# SoundChip.net
KiCad netlist of a schematic drawn in Altium Designer
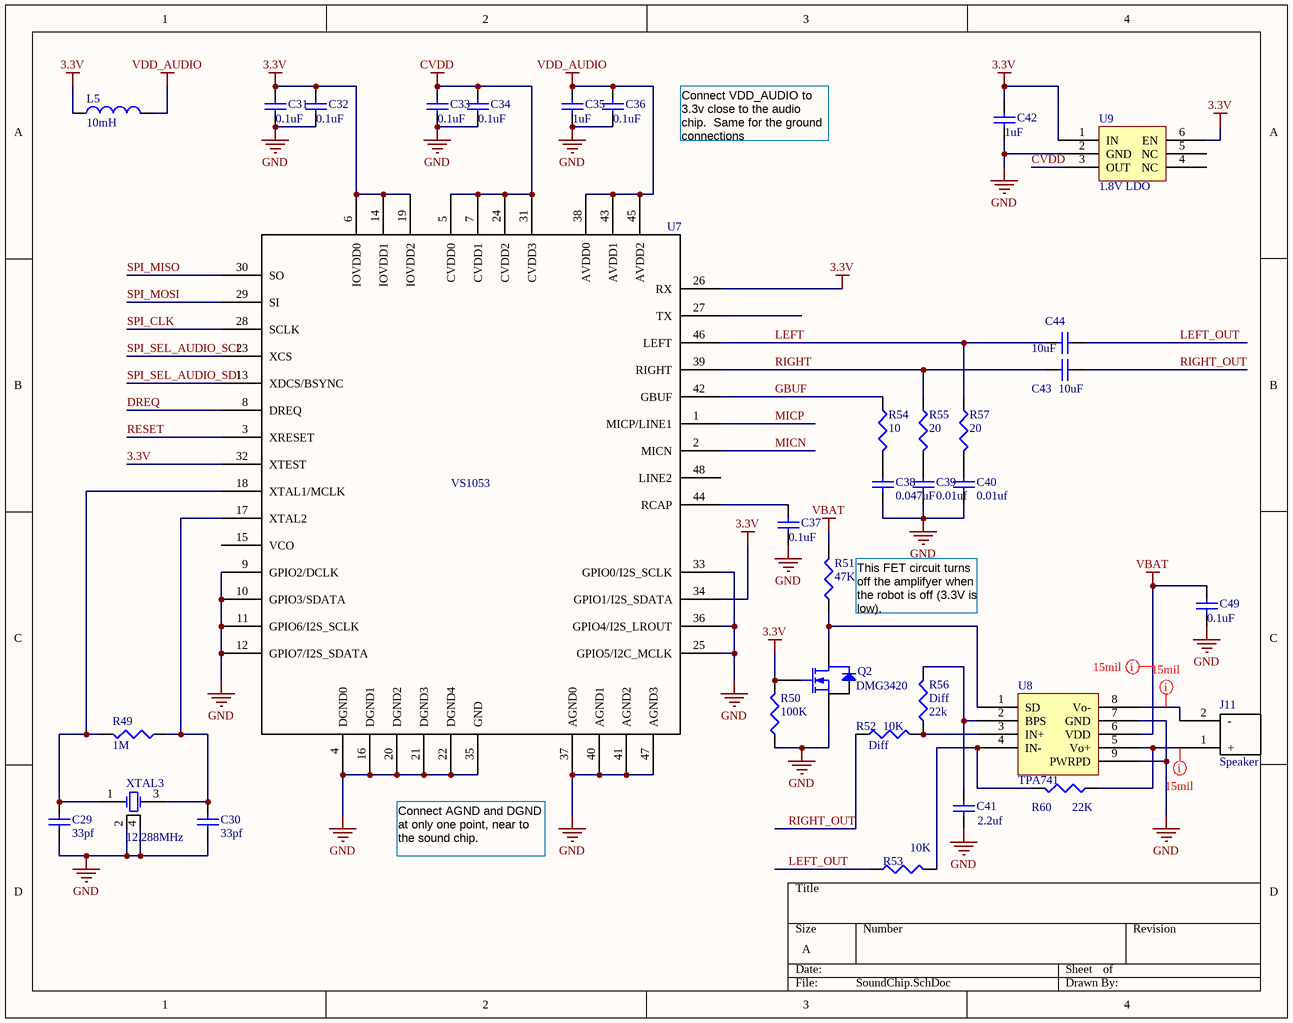
[diagram p0: SoundChip.SchDoc]

(export (version "E")
  (design (tool "Eeschema 10.0.6"))
  (components
    (comp (ref "C29")
      (value "33pf")
      (footprint "CAPC1005L")
      (description "Capacitor (Semiconductor SIM Model)")
      (fields
        (field (name "PART NUMBER") "GRM1555C1H330JA01D")
        (field (name "MANUFACTURER") "Murata")
        (field (name "PUBLISHER") "Altium Limited")
      )
      (libsource (lib "Miscellaneous Devices") (part "Cap Semi"))
    )
    (comp (ref "C30")
      (value "33pf")
      (footprint "CAPC1005L")
      (description "Capacitor (Semiconductor SIM Model)")
      (fields
        (field (name "PART NUMBER") "GRM1555C1H330JA01D")
        (field (name "MANUFACTURER") "Murata")
        (field (name "PUBLISHER") "Altium Limited")
      )
      (libsource (lib "Miscellaneous Devices") (part "Cap Semi"))
    )
    (comp (ref "C31")
      (value "0.1uF")
      (footprint "CAPC1005L")
      (description "Capacitor (Semiconductor SIM Model)")
      (fields
        (field (name "PART NUMBER") "C1005X5R1A104M050BA")
        (field (name "MANUFACTURER") "TDK")
        (field (name "PUBLISHER") "Altium Limited")
      )
      (libsource (lib "Miscellaneous Devices") (part "Cap Semi"))
    )
    (comp (ref "C32")
      (value "0.1uF")
      (footprint "CAPC1005L")
      (description "Capacitor (Semiconductor SIM Model)")
      (fields
        (field (name "PART NUMBER") "C1005X5R1A104M050BA")
        (field (name "MANUFACTURER") "TDK")
        (field (name "PUBLISHER") "Altium Limited")
      )
      (libsource (lib "Miscellaneous Devices") (part "Cap Semi"))
    )
    (comp (ref "C33")
      (value "0.1uF")
      (footprint "CAPC1005L")
      (description "Capacitor (Semiconductor SIM Model)")
      (fields
        (field (name "PART NUMBER") "C1005X5R1A104M050BA")
        (field (name "MANUFACTURER") "TDK")
        (field (name "PUBLISHER") "Altium Limited")
      )
      (libsource (lib "Miscellaneous Devices") (part "Cap Semi"))
    )
    (comp (ref "C34")
      (value "0.1uF")
      (footprint "CAPC1005L")
      (description "Capacitor (Semiconductor SIM Model)")
      (fields
        (field (name "PART NUMBER") "C1005X5R1A104M050BA")
        (field (name "MANUFACTURER") "TDK")
        (field (name "PUBLISHER") "Altium Limited")
      )
      (libsource (lib "Miscellaneous Devices") (part "Cap Semi"))
    )
    (comp (ref "C35")
      (value "1uF")
      (footprint "CAPC1608L")
      (description "Capacitor (Semiconductor SIM Model)")
      (fields
        (field (name "PART NUMBER") "C1608Y5V1C105Z")
        (field (name "MANUFACTURER") "TDK")
        (field (name "PUBLISHER") "Altium Limited")
      )
      (libsource (lib "Miscellaneous Devices") (part "Cap Semi"))
    )
    (comp (ref "C36")
      (value "0.1uF")
      (footprint "CAPC1005L")
      (description "Capacitor (Semiconductor SIM Model)")
      (fields
        (field (name "PART NUMBER") "C1005X5R1A104M050BA")
        (field (name "MANUFACTURER") "TDK")
        (field (name "PUBLISHER") "Altium Limited")
      )
      (libsource (lib "Miscellaneous Devices") (part "Cap Semi"))
    )
    (comp (ref "C37")
      (value "0.1uF")
      (footprint "CAPC1005L")
      (description "Capacitor (Semiconductor SIM Model)")
      (fields
        (field (name "PART NUMBER") "C1005X5R1A104M050BA")
        (field (name "MANUFACTURER") "TDK")
        (field (name "PUBLISHER") "Altium Limited")
      )
      (libsource (lib "Miscellaneous Devices") (part "Cap Semi"))
    )
    (comp (ref "C38")
      (value "0.047uF")
      (footprint "CAPC1005L")
      (description "Capacitor (Semiconductor SIM Model)")
      (fields
        (field (name "PART NUMBER") "CGA2BZX7R1C473K")
        (field (name "PART NUMBER_1") "CGA2B2X7R1C473K050BA")
        (field (name "PUBLISHER") "Altium Limited")
      )
      (libsource (lib "Miscellaneous Devices") (part "Cap Semi"))
    )
    (comp (ref "C39")
      (value "0.01uf")
      (footprint "CAPC1005L")
      (description "Capacitor (Semiconductor SIM Model)")
      (fields
        (field (name "PART NUMBER") "C1005X7R1C103K050BA")
        (field (name "MANUFACTURER") "TDK")
        (field (name "PUBLISHER") "Altium Limited")
      )
      (libsource (lib "Miscellaneous Devices") (part "Cap Semi"))
    )
    (comp (ref "C40")
      (value "0.01uf")
      (footprint "CAPC1005L")
      (description "Capacitor (Semiconductor SIM Model)")
      (fields
        (field (name "PART NUMBER") "C1005X7R1C103K050BA")
        (field (name "MANUFACTURER") "TDK")
        (field (name "PUBLISHER") "Altium Limited")
      )
      (libsource (lib "Miscellaneous Devices") (part "Cap Semi"))
    )
    (comp (ref "C41")
      (value "2.2uf")
      (footprint "J1-0603")
      (description "Capacitor (Semiconductor SIM Model)")
      (fields
        (field (name "PART NUMBER") "JMK107F225ZA-T")
        (field (name "MANUFACTURER") "Taiyo Yuden")
        (field (name "PUBLISHER") "Altium Limited")
      )
      (libsource (lib "Miscellaneous Devices") (part "Cap Semi"))
    )
    (comp (ref "C42")
      (value "1uF")
      (footprint "CAPC1608L")
      (description "Capacitor (Semiconductor SIM Model)")
      (fields
        (field (name "PART NUMBER") "C1608Y5V1C105Z")
        (field (name "MANUFACTURER") "TDK")
        (field (name "PUBLISHER") "Altium Limited")
      )
      (libsource (lib "Miscellaneous Devices") (part "Cap Semi"))
    )
    (comp (ref "C43")
      (value "10uF")
      (footprint "CAPC1608L")
      (description "Capacitor (Semiconductor SIM Model)")
      (fields
        (field (name "PART NUMBER") "GRM188R60J106ME47J")
        (field (name "MANUFACTURER") "Murata")
        (field (name "PUBLISHER") "Altium Limited")
      )
      (libsource (lib "Miscellaneous Devices") (part "Cap Semi"))
    )
    (comp (ref "C44")
      (value "10uF")
      (footprint "CAPC1608L")
      (description "Capacitor (Semiconductor SIM Model)")
      (fields
        (field (name "PART NUMBER") "GRM188R60J106ME47J")
        (field (name "MANUFACTURER") "Murata")
        (field (name "PUBLISHER") "Altium Limited")
      )
      (libsource (lib "Miscellaneous Devices") (part "Cap Semi"))
    )
    (comp (ref "C49")
      (value "0.1uF")
      (footprint "CAPC1005L")
      (description "Capacitor (Semiconductor SIM Model)")
      (fields
        (field (name "PART NUMBER") "C1005X5R1A104M050BA")
        (field (name "MANUFACTURER") "TDK")
        (field (name "PUBLISHER") "Altium Limited")
      )
      (libsource (lib "Miscellaneous Devices") (part "Cap Semi"))
    )
    (comp (ref "J11")
      (value "Speaker")
      (footprint "BatteryConnJST")
      (fields (field (name "PART NUMBER") "530140210") (field (name "MANUFACTURER") "Molex"))
      (libsource (lib "mrone") (part "BatteryConnJST"))
    )
    (comp (ref "L5")
      (value "10mH")
      (footprint "INDC2012L")
      (description "Inductor")
      (fields
        (field (name "PART NUMBER") "MMZ2012R102A")
        (field (name "MANUFACTURER") "TDK")
        (field (name "PUBLISHER") "Altium Limited")
      )
      (libsource (lib "Miscellaneous Devices") (part "Inductor"))
    )
    (comp (ref "Q2")
      (value "N-Mosfet")
      (footprint "SOT-23")
      (fields
        (field (name "MPN") "DMG3420")
        (field (name "PART NUMBER") "DMG3420U-7")
        (field (name "MANUFACTURER") "Diodes")
      )
      (libsource (lib "mrone") (part "N-Mosfet"))
    )
    (comp (ref "R49")
      (value "1M")
      (footprint "RESC1608L")
      (description "Resistor")
      (fields
        (field (name "PART NUMBER") "CR0603-JW-105GLF")
        (field (name "MANUFACTURER") "Bourns")
        (field (name "PUBLISHER") "Altium Limited")
      )
      (libsource (lib "Miscellaneous Devices") (part "Res3"))
    )
    (comp (ref "R50")
      (value "100K")
      (footprint "RESC1608L")
      (description "Resistor")
      (fields
        (field (name "PART NUMBER") "ERJ-3GEYJ104V")
        (field (name "MANUFACTURER") "Panasonic")
        (field (name "PUBLISHER") "Altium Limited")
      )
      (libsource (lib "Miscellaneous Devices") (part "Res3"))
    )
    (comp (ref "R51")
      (value "47K")
      (footprint "J1-0603")
      (description "Resistor")
      (fields
        (field (name "PART NUMBER") "ERJ-3GEYJ473V")
        (field (name "MANUFACTURER") "Panasonic")
        (field (name "PUBLISHER") "Altium Limited")
      )
      (libsource (lib "Miscellaneous Devices") (part "Res3"))
    )
    (comp (ref "R52")
      (value "Diff")
      (footprint "RESC1608L")
      (description "Resistor")
      (fields
        (field (name "ALTIUM_VALUE") "10K")
        (field (name "PART NUMBER") "SR03-1002")
        (field (name "MANUFACTURER") "Vishay")
        (field (name "PUBLISHER") "Altium Limited")
      )
      (libsource (lib "Miscellaneous Devices") (part "Res3"))
    )
    (comp (ref "R53")
      (value "10K")
      (footprint "RESC1608L")
      (description "Resistor")
      (fields
        (field (name "PART NUMBER") "SR03-1002")
        (field (name "MANUFACTURER") "Vishay")
        (field (name "PUBLISHER") "Altium Limited")
      )
      (libsource (lib "Miscellaneous Devices") (part "Res3"))
    )
    (comp (ref "R54")
      (value "10")
      (footprint "RESC1608L")
      (description "Resistor")
      (fields
        (field (name "PART NUMBER") "RMCF0603JT10R0")
        (field (name "MANUFACTURER") "Stackpole")
        (field (name "PUBLISHER") "Altium Limited")
      )
      (libsource (lib "Miscellaneous Devices") (part "Res3"))
    )
    (comp (ref "R55")
      (value "20")
      (footprint "RESC1608L")
      (description "Resistor")
      (fields
        (field (name "PART NUMBER") "RMCF0603FT20R0")
        (field (name "MANUFACTURER") "Stack Pole")
        (field (name "PUBLISHER") "Altium Limited")
      )
      (libsource (lib "Miscellaneous Devices") (part "Res3"))
    )
    (comp (ref "R56")
      (value "Diff")
      (footprint "RESC1608L")
      (description "Resistor")
      (fields
        (field (name "ALTIUM_VALUE") "22k")
        (field (name "MANUFACTURER") "Panasonic")
        (field (name "PUBLISHER") "Altium Limited")
      )
      (libsource (lib "Miscellaneous Devices") (part "Res3"))
    )
    (comp (ref "R57")
      (value "20")
      (footprint "RESC1608L")
      (description "Resistor")
      (fields
        (field (name "PART NUMBER") "RMCF0603FT20R0")
        (field (name "MANUFACTURER") "Stack Pole")
        (field (name "PUBLISHER") "Altium Limited")
      )
      (libsource (lib "Miscellaneous Devices") (part "Res3"))
    )
    (comp (ref "R60")
      (value "22K")
      (footprint "RESC1608L")
      (description "Resistor")
      (fields
        (field (name "PART NUMBER") "ERJ-3GEYJ223V")
        (field (name "MANUFACTURER") "Panasonic")
        (field (name "PUBLISHER") "Altium Limited")
      )
      (libsource (lib "Miscellaneous Devices") (part "Res3"))
    )
    (comp (ref "U7")
      (value "VS1053")
      (footprint "LQFP-48")
      (fields (field (name "MANUFACTURER") "VLSI Solution"))
      (libsource (lib "mrone") (part "VS1053"))
    )
    (comp (ref "U8")
      (value "TPA741")
      (footprint "audio amp")
      (fields (field (name "PART NUMBER") "TPA741DGNR") (field (name "MANUFACTURER") "TI"))
      (libsource (lib "mrone") (part "Audio Amp TPA741"))
    )
    (comp (ref "U9")
      (value "1.8V LDO")
      (footprint "WFDFN-6")
      (fields (field (name "PART NUMBER") "TLV70018DSET") (field (name "MANUFACTURER") "TI"))
      (libsource (lib "mrone") (part "1.8V_LDO"))
    )
    (comp (ref "XTAL3")
      (value "12.288MHz")
      (footprint "CRYSTAL")
      (fields (field (name "PART NUMBER") "ABM3B-12.288MHZ-10-1-U-T") (field (name "MANUFACTURER") "Abracon"))
      (libsource (lib "mrone") (part "Crystal"))
    )
  )
  (nets
    (net (code "1") (name "/DREQ") (class "Default")
      (node (ref "U7") (pin "8") (pinfunction "DREQ_8") (pintype "passive"))
    )
    (net (code "2") (name "/GBUF") (class "Default")
      (node (ref "R54") (pin "1") (pinfunction "1_1") (pintype "passive"))
      (node (ref "U7") (pin "42") (pinfunction "GBUF_42") (pintype "passive"))
    )
    (net (code "3") (name "/LEFT") (class "Default")
      (node (ref "C44") (pin "2") (pinfunction "2_2") (pintype "passive"))
      (node (ref "R57") (pin "1") (pinfunction "1_1") (pintype "passive"))
      (node (ref "U7") (pin "46") (pinfunction "LEFT_46") (pintype "passive"))
    )
    (net (code "4") (name "/LEFT_OUT") (class "Default")
      (node (ref "C44") (pin "1") (pinfunction "1_1") (pintype "passive"))
      (node (ref "R53") (pin "1") (pinfunction "1_1") (pintype "passive"))
    )
    (net (code "5") (name "/MICN") (class "Default")
      (node (ref "U7") (pin "2") (pinfunction "MICN_2") (pintype "passive"))
    )
    (net (code "6") (name "/MICP") (class "Default")
      (node (ref "U7") (pin "1") (pinfunction "MICP/LINE1_1") (pintype "passive"))
    )
    (net (code "7") (name "/RESET") (class "Default")
      (node (ref "U7") (pin "3") (pinfunction "XRESET_3") (pintype "passive"))
    )
    (net (code "8") (name "/RIGHT") (class "Default")
      (node (ref "C43") (pin "2") (pinfunction "2_2") (pintype "passive"))
      (node (ref "R55") (pin "1") (pinfunction "1_1") (pintype "passive"))
      (node (ref "U7") (pin "39") (pinfunction "RIGHT_39") (pintype "passive"))
    )
    (net (code "9") (name "/RIGHT_OUT") (class "Default")
      (node (ref "C43") (pin "1") (pinfunction "1_1") (pintype "passive"))
      (node (ref "R52") (pin "1") (pinfunction "1_1") (pintype "passive"))
    )
    (net (code "10") (name "/SPI_CLK") (class "Default")
      (node (ref "U7") (pin "28") (pinfunction "SCLK_28") (pintype "passive"))
    )
    (net (code "11") (name "/SPI_MISO") (class "Default")
      (node (ref "U7") (pin "30") (pinfunction "SO_30") (pintype "passive"))
    )
    (net (code "12") (name "/SPI_MOSI") (class "Default")
      (node (ref "U7") (pin "29") (pinfunction "SI_29") (pintype "passive"))
    )
    (net (code "13") (name "/SPI_SEL_AUDIO_SCI") (class "Default")
      (node (ref "U7") (pin "23") (pinfunction "XCS_23") (pintype "passive"))
    )
    (net (code "14") (name "/SPI_SEL_AUDIO_SDI") (class "Default")
      (node (ref "U7") (pin "13") (pinfunction "XDCS/BSYNC_13") (pintype "passive"))
    )
    (net (code "15") (name "3.3V") (class "Default")
      (node (ref "C31") (pin "2") (pinfunction "2_2") (pintype "passive"))
      (node (ref "C32") (pin "2") (pinfunction "2_2") (pintype "passive"))
      (node (ref "C42") (pin "1") (pinfunction "1_1") (pintype "passive"))
      (node (ref "L5") (pin "2") (pinfunction "2_2") (pintype "passive"))
      (node (ref "Q2") (pin "1") (pinfunction "G_1") (pintype "passive"))
      (node (ref "R50") (pin "2") (pinfunction "2_2") (pintype "passive"))
      (node (ref "U7") (pin "14") (pinfunction "IOVDD1_14") (pintype "passive"))
      (node (ref "U7") (pin "19") (pinfunction "IOVDD2_19") (pintype "passive"))
      (node (ref "U7") (pin "26") (pinfunction "RX_26") (pintype "passive"))
      (node (ref "U7") (pin "32") (pinfunction "XTEST_32") (pintype "passive"))
      (node (ref "U7") (pin "34") (pinfunction "GPIO1/I2S_SDATA_34") (pintype "passive"))
      (node (ref "U7") (pin "6") (pinfunction "IOVDD0_6") (pintype "passive"))
      (node (ref "U9") (pin "1") (pinfunction "IN_1") (pintype "passive"))
      (node (ref "U9") (pin "6") (pinfunction "EN_6") (pintype "passive"))
    )
    (net (code "16") (name "CVDD") (class "Default")
      (node (ref "C33") (pin "2") (pinfunction "2_2") (pintype "passive"))
      (node (ref "C34") (pin "2") (pinfunction "2_2") (pintype "passive"))
      (node (ref "U7") (pin "24") (pinfunction "CVDD2_24") (pintype "passive"))
      (node (ref "U7") (pin "31") (pinfunction "CVDD3_31") (pintype "passive"))
      (node (ref "U7") (pin "5") (pinfunction "CVDD0_5") (pintype "passive"))
      (node (ref "U7") (pin "7") (pinfunction "CVDD1_7") (pintype "passive"))
      (node (ref "U9") (pin "3") (pinfunction "OUT_3") (pintype "passive"))
    )
    (net (code "17") (name "GND") (class "Default")
      (node (ref "C29") (pin "2") (pinfunction "2_2") (pintype "passive"))
      (node (ref "C30") (pin "2") (pinfunction "2_2") (pintype "passive"))
      (node (ref "C31") (pin "1") (pinfunction "1_1") (pintype "passive"))
      (node (ref "C32") (pin "1") (pinfunction "1_1") (pintype "passive"))
      (node (ref "C33") (pin "1") (pinfunction "1_1") (pintype "passive"))
      (node (ref "C34") (pin "1") (pinfunction "1_1") (pintype "passive"))
      (node (ref "C35") (pin "2") (pinfunction "2_2") (pintype "passive"))
      (node (ref "C36") (pin "1") (pinfunction "1_1") (pintype "passive"))
      (node (ref "C37") (pin "1") (pinfunction "1_1") (pintype "passive"))
      (node (ref "C38") (pin "2") (pinfunction "2_2") (pintype "passive"))
      (node (ref "C39") (pin "2") (pinfunction "2_2") (pintype "passive"))
      (node (ref "C40") (pin "2") (pinfunction "2_2") (pintype "passive"))
      (node (ref "C41") (pin "1") (pinfunction "1_1") (pintype "passive"))
      (node (ref "C42") (pin "2") (pinfunction "2_2") (pintype "passive"))
      (node (ref "C49") (pin "1") (pinfunction "1_1") (pintype "passive"))
      (node (ref "Q2") (pin "2") (pinfunction "S_2") (pintype "passive"))
      (node (ref "R50") (pin "1") (pinfunction "1_1") (pintype "passive"))
      (node (ref "U7") (pin "10") (pinfunction "GPIO3/SDATA_10") (pintype "passive"))
      (node (ref "U7") (pin "11") (pinfunction "GPIO6/I2S_SCLK_11") (pintype "passive"))
      (node (ref "U7") (pin "12") (pinfunction "GPIO7/I2S_SDATA_12") (pintype "passive"))
      (node (ref "U7") (pin "16") (pinfunction "DGND1_16") (pintype "passive"))
      (node (ref "U7") (pin "20") (pinfunction "DGND2_20") (pintype "passive"))
      (node (ref "U7") (pin "21") (pinfunction "DGND3_21") (pintype "passive"))
      (node (ref "U7") (pin "22") (pinfunction "DGND4_22") (pintype "passive"))
      (node (ref "U7") (pin "25") (pinfunction "GPIO5/I2C_MCLK_25") (pintype "passive"))
      (node (ref "U7") (pin "33") (pinfunction "GPIO0/I2S_SCLK_33") (pintype "passive"))
      (node (ref "U7") (pin "35") (pinfunction "GND_35") (pintype "passive"))
      (node (ref "U7") (pin "36") (pinfunction "GPIO4/I2S_LROUT_36") (pintype "passive"))
      (node (ref "U7") (pin "37") (pinfunction "AGND0_37") (pintype "passive"))
      (node (ref "U7") (pin "4") (pinfunction "DGND0_4") (pintype "passive"))
      (node (ref "U7") (pin "40") (pinfunction "AGND1_40") (pintype "passive"))
      (node (ref "U7") (pin "41") (pinfunction "AGND2_41") (pintype "passive"))
      (node (ref "U7") (pin "47") (pinfunction "AGND3_47") (pintype "passive"))
      (node (ref "U7") (pin "9") (pinfunction "GPIO2/DCLK_9") (pintype "passive"))
      (node (ref "U8") (pin "7") (pinfunction "GND_7") (pintype "passive"))
      (node (ref "U8") (pin "9") (pinfunction "PWRPD_9") (pintype "passive"))
      (node (ref "U9") (pin "2") (pinfunction "GND_2") (pintype "passive"))
      (node (ref "XTAL3") (pin "2") (pinfunction "GND_2") (pintype "passive"))
      (node (ref "XTAL3") (pin "4") (pinfunction "GND_4") (pintype "passive"))
    )
    (net (code "18") (name "Net-(C38-Pad1)") (class "Default")
      (node (ref "C38") (pin "1") (pinfunction "1_1") (pintype "passive"))
      (node (ref "R54") (pin "2") (pinfunction "2_2") (pintype "passive"))
    )
    (net (code "19") (name "Net-(C39-Pad1)") (class "Default")
      (node (ref "C39") (pin "1") (pinfunction "1_1") (pintype "passive"))
      (node (ref "R55") (pin "2") (pinfunction "2_2") (pintype "passive"))
    )
    (net (code "20") (name "Net-(C40-Pad1)") (class "Default")
      (node (ref "C40") (pin "1") (pinfunction "1_1") (pintype "passive"))
      (node (ref "R57") (pin "2") (pinfunction "2_2") (pintype "passive"))
    )
    (net (code "21") (name "Net-(J11-+)") (class "Default")
      (node (ref "J11") (pin "1") (pinfunction "+_1") (pintype "passive"))
      (node (ref "R60") (pin "1") (pinfunction "1_1") (pintype "passive"))
      (node (ref "U8") (pin "5") (pinfunction "Vo+_5") (pintype "passive"))
    )
    (net (code "22") (name "Net-(J11--)") (class "Default")
      (node (ref "J11") (pin "2") (pinfunction "-_2") (pintype "passive"))
      (node (ref "U8") (pin "8") (pinfunction "Vo-_8") (pintype "passive"))
    )
    (net (code "23") (name "Net-(Q2-D)") (class "Default")
      (node (ref "Q2") (pin "3") (pinfunction "D_3") (pintype "passive"))
      (node (ref "R51") (pin "1") (pinfunction "1_1") (pintype "passive"))
      (node (ref "U8") (pin "1") (pinfunction "SD_1") (pintype "passive"))
    )
    (net (code "24") (name "Net-(U7-RCAP)") (class "Default")
      (node (ref "C37") (pin "2") (pinfunction "2_2") (pintype "passive"))
      (node (ref "U7") (pin "44") (pinfunction "RCAP_44") (pintype "passive"))
    )
    (net (code "25") (name "Net-(U7-XTAL1{slash}MCLK)") (class "Default")
      (node (ref "C29") (pin "1") (pinfunction "1_1") (pintype "passive"))
      (node (ref "R49") (pin "2") (pinfunction "2_2") (pintype "passive"))
      (node (ref "U7") (pin "18") (pinfunction "XTAL1/MCLK_18") (pintype "passive"))
      (node (ref "XTAL3") (pin "1") (pinfunction "OSC1_1") (pintype "passive"))
    )
    (net (code "26") (name "Net-(U7-XTAL2)") (class "Default")
      (node (ref "C30") (pin "1") (pinfunction "1_1") (pintype "passive"))
      (node (ref "R49") (pin "1") (pinfunction "1_1") (pintype "passive"))
      (node (ref "U7") (pin "17") (pinfunction "XTAL2_17") (pintype "passive"))
      (node (ref "XTAL3") (pin "3") (pinfunction "OSC2_3") (pintype "passive"))
    )
    (net (code "27") (name "Net-(U8-BPS)") (class "Default")
      (node (ref "C41") (pin "2") (pinfunction "2_2") (pintype "passive"))
      (node (ref "R56") (pin "2") (pinfunction "2_2") (pintype "passive"))
      (node (ref "U8") (pin "2") (pinfunction "BPS_2") (pintype "passive"))
    )
    (net (code "28") (name "Net-(U8-IN+)") (class "Default")
      (node (ref "R52") (pin "2") (pinfunction "2_2") (pintype "passive"))
      (node (ref "R56") (pin "1") (pinfunction "1_1") (pintype "passive"))
      (node (ref "U8") (pin "3") (pinfunction "IN+_3") (pintype "passive"))
    )
    (net (code "29") (name "Net-(U8-IN-)") (class "Default")
      (node (ref "R53") (pin "2") (pinfunction "2_2") (pintype "passive"))
      (node (ref "R60") (pin "2") (pinfunction "2_2") (pintype "passive"))
      (node (ref "U8") (pin "4") (pinfunction "IN-_4") (pintype "passive"))
    )
    (net (code "30") (name "VBAT") (class "Default")
      (node (ref "C49") (pin "2") (pinfunction "2_2") (pintype "passive"))
      (node (ref "R51") (pin "2") (pinfunction "2_2") (pintype "passive"))
      (node (ref "U8") (pin "6") (pinfunction "VDD_6") (pintype "passive"))
    )
    (net (code "31") (name "VDD_AUDIO") (class "Default")
      (node (ref "C35") (pin "1") (pinfunction "1_1") (pintype "passive"))
      (node (ref "C36") (pin "2") (pinfunction "2_2") (pintype "passive"))
      (node (ref "L5") (pin "1") (pinfunction "1_1") (pintype "passive"))
      (node (ref "U7") (pin "38") (pinfunction "AVDD0_38") (pintype "passive"))
      (node (ref "U7") (pin "43") (pinfunction "AVDD1_43") (pintype "passive"))
      (node (ref "U7") (pin "45") (pinfunction "AVDD2_45") (pintype "passive"))
    )
    (net (code "32") (name "unconnected-(U7-LINE2-Pad48)") (class "Default")
      (node (ref "U7") (pin "48") (pinfunction "LINE2_48") (pintype "passive"))
    )
    (net (code "33") (name "unconnected-(U7-TX-Pad27)") (class "Default")
      (node (ref "U7") (pin "27") (pinfunction "TX_27") (pintype "passive"))
    )
    (net (code "34") (name "unconnected-(U7-VCO-Pad15)") (class "Default")
      (node (ref "U7") (pin "15") (pinfunction "VCO_15") (pintype "passive"))
    )
    (net (code "35") (name "unconnected-(U9-NC-Pad4)") (class "Default")
      (node (ref "U9") (pin "4") (pinfunction "NC_4") (pintype "passive"))
    )
    (net (code "36") (name "unconnected-(U9-NC-Pad5)") (class "Default")
      (node (ref "U9") (pin "5") (pinfunction "NC_5") (pintype "passive"))
    )
  )
)
